# v1_1.net
KiCad netlist of a schematic drawn in EAGLE
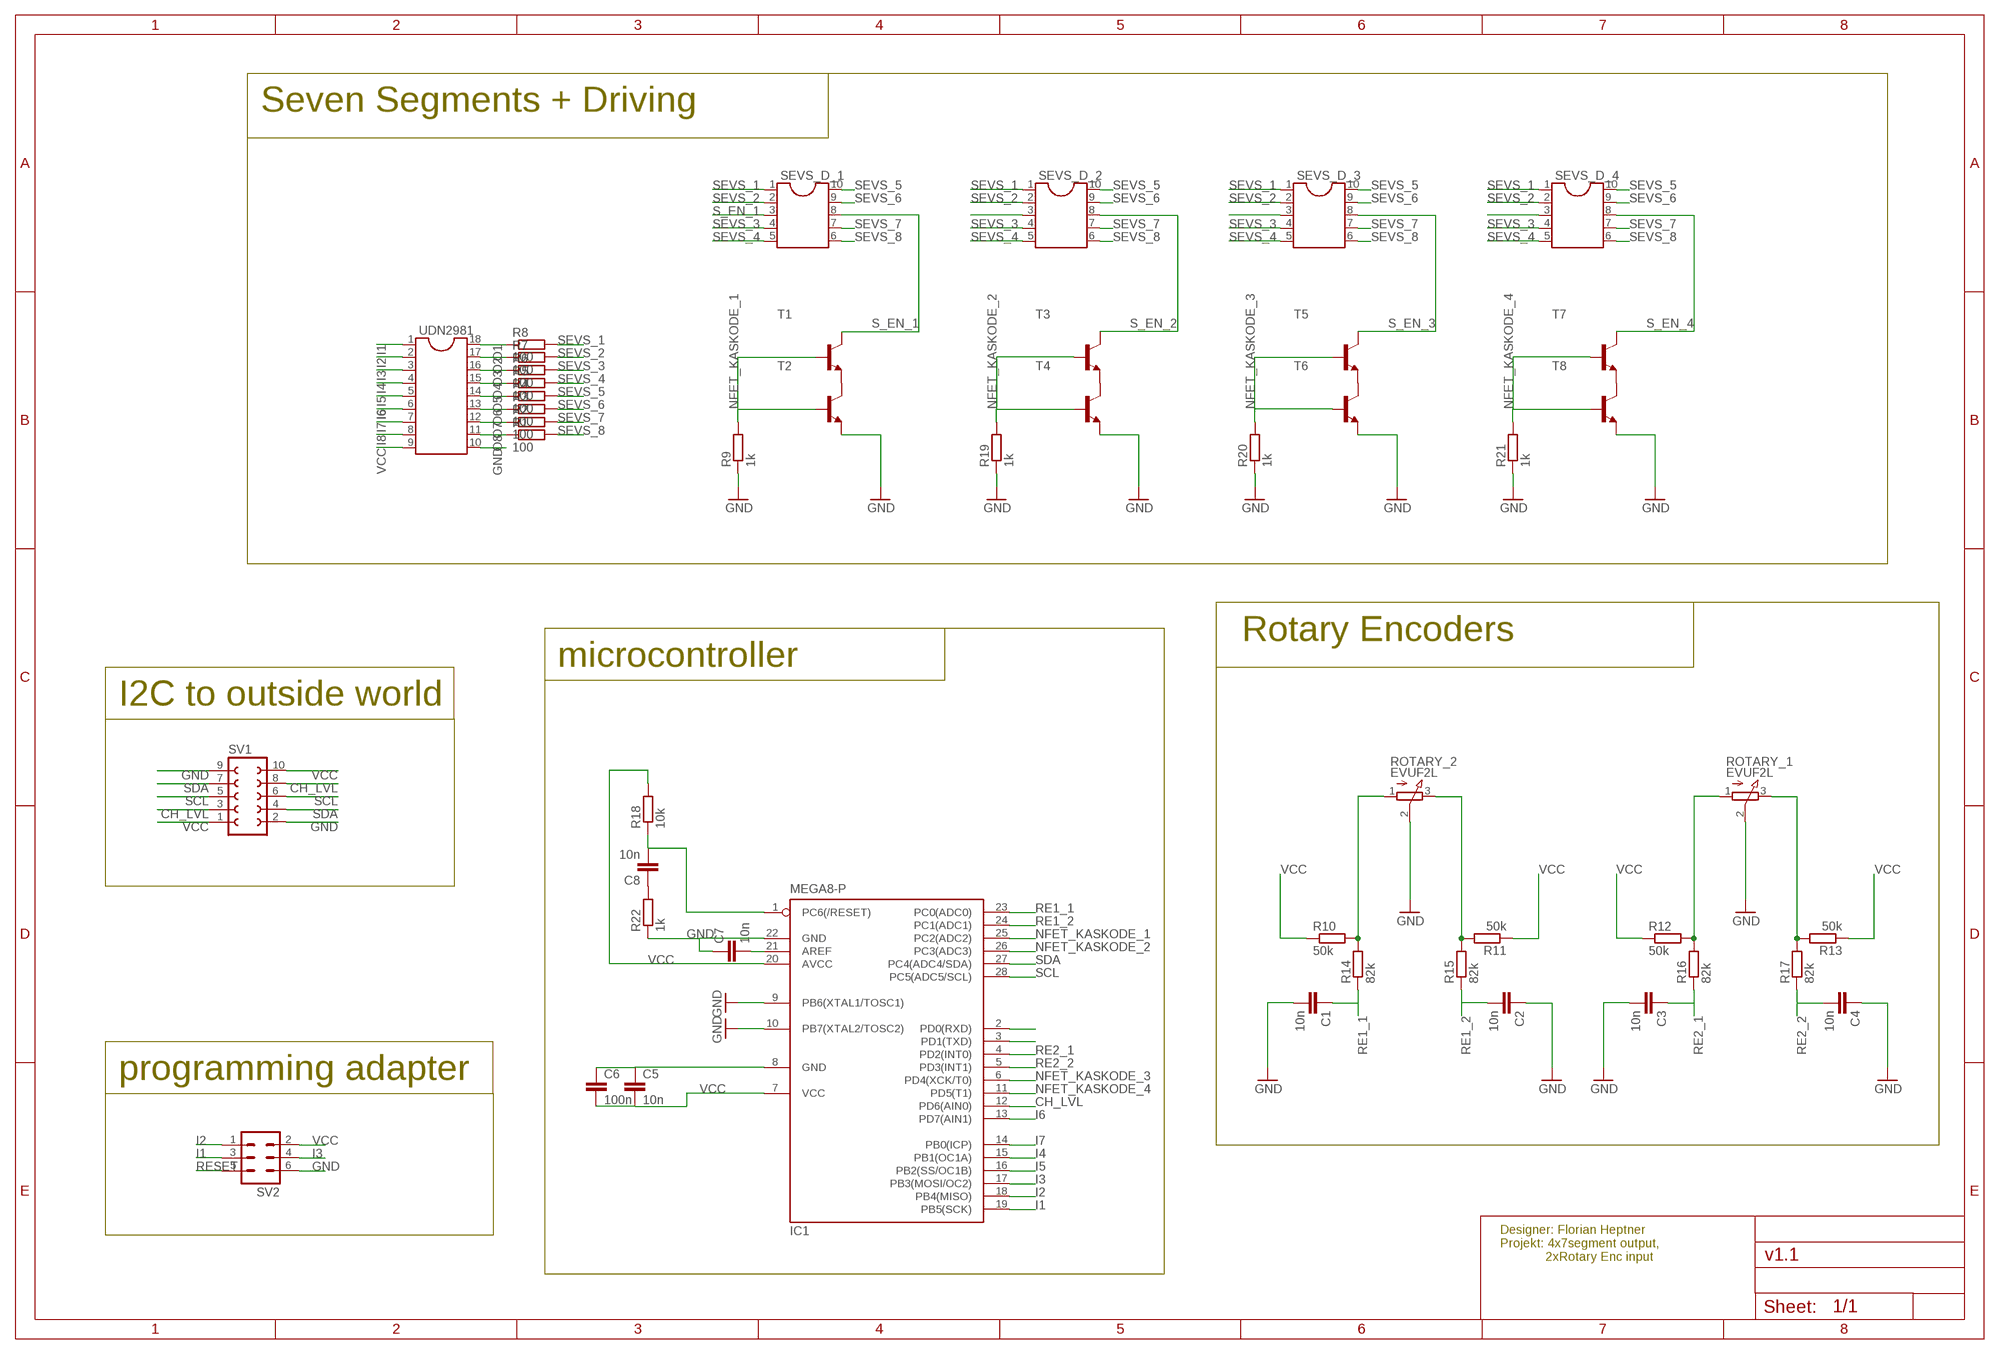
[diagram p0: schematic, sheet 1]

(export (version "E")
  (design (tool "Eeschema 10.0.6"))
  (components
    (comp (ref "C1")
      (value "10n")
      (footprint "eagle-import:C2.5-3")
      (libsource (lib "eagle-import") (part "C2,5-3"))
    )
    (comp (ref "C2")
      (value "10n")
      (footprint "eagle-import:C2.5-3")
      (libsource (lib "eagle-import") (part "C2,5-3"))
    )
    (comp (ref "C3")
      (value "10n")
      (footprint "eagle-import:C2.5-3")
      (libsource (lib "eagle-import") (part "C2,5-3"))
    )
    (comp (ref "C4")
      (value "10n")
      (footprint "eagle-import:C2.5-3")
      (libsource (lib "eagle-import") (part "C2,5-3"))
    )
    (comp (ref "C5")
      (value "10n")
      (footprint "eagle-import:C2.5-3")
      (libsource (lib "eagle-import") (part "C2,5-3"))
    )
    (comp (ref "C6")
      (value "100n")
      (footprint "eagle-import:C2.5-3")
      (libsource (lib "eagle-import") (part "C2,5-3"))
    )
    (comp (ref "C7")
      (value "10n")
      (footprint "eagle-import:C2.5-3")
      (libsource (lib "eagle-import") (part "C2,5-3"))
    )
    (comp (ref "C8")
      (value "10n")
      (footprint "eagle-import:C2.5-3")
      (libsource (lib "eagle-import") (part "C2,5-3"))
    )
    (comp (ref "IC1")
      (value "MEGA8-P")
      (footprint "eagle-import:DIL28-3")
      (libsource (lib "eagle-import") (part "MEGA8-P"))
    )
    (comp (ref "R1")
      (value "100")
      (footprint "eagle-import:0207_10")
      (libsource (lib "eagle-import") (part "R-EU_0207/10"))
    )
    (comp (ref "R2")
      (value "100")
      (footprint "eagle-import:0207_10")
      (libsource (lib "eagle-import") (part "R-EU_0207/10"))
    )
    (comp (ref "R3")
      (value "100")
      (footprint "eagle-import:0207_10")
      (libsource (lib "eagle-import") (part "R-EU_0207/10"))
    )
    (comp (ref "R4")
      (value "100")
      (footprint "eagle-import:0207_10")
      (libsource (lib "eagle-import") (part "R-EU_0207/10"))
    )
    (comp (ref "R5")
      (value "100")
      (footprint "eagle-import:0207_10")
      (libsource (lib "eagle-import") (part "R-EU_0207/10"))
    )
    (comp (ref "R6")
      (value "100")
      (footprint "eagle-import:0207_10")
      (libsource (lib "eagle-import") (part "R-EU_0207/10"))
    )
    (comp (ref "R7")
      (value "100")
      (footprint "eagle-import:0207_10")
      (libsource (lib "eagle-import") (part "R-EU_0207/10"))
    )
    (comp (ref "R8")
      (value "100")
      (footprint "eagle-import:0207_10")
      (libsource (lib "eagle-import") (part "R-EU_0207/10"))
    )
    (comp (ref "R9")
      (value "1k")
      (footprint "eagle-import:0207_10")
      (libsource (lib "eagle-import") (part "R-EU_0207/10"))
    )
    (comp (ref "R10")
      (value "50k")
      (footprint "eagle-import:0207_10")
      (libsource (lib "eagle-import") (part "R-EU_0207/10"))
    )
    (comp (ref "R11")
      (value "50k")
      (footprint "eagle-import:0207_10")
      (libsource (lib "eagle-import") (part "R-EU_0207/10"))
    )
    (comp (ref "R12")
      (value "50k")
      (footprint "eagle-import:0207_10")
      (libsource (lib "eagle-import") (part "R-EU_0207/10"))
    )
    (comp (ref "R13")
      (value "50k")
      (footprint "eagle-import:0207_10")
      (libsource (lib "eagle-import") (part "R-EU_0207/10"))
    )
    (comp (ref "R14")
      (value "82k")
      (footprint "eagle-import:0207_10")
      (libsource (lib "eagle-import") (part "R-EU_0207/10"))
    )
    (comp (ref "R15")
      (value "82k")
      (footprint "eagle-import:0207_10")
      (libsource (lib "eagle-import") (part "R-EU_0207/10"))
    )
    (comp (ref "R16")
      (value "82k")
      (footprint "eagle-import:0207_10")
      (libsource (lib "eagle-import") (part "R-EU_0207/10"))
    )
    (comp (ref "R17")
      (value "82k")
      (footprint "eagle-import:0207_10")
      (libsource (lib "eagle-import") (part "R-EU_0207/10"))
    )
    (comp (ref "R18")
      (value "10k")
      (footprint "eagle-import:0207_10")
      (libsource (lib "eagle-import") (part "R-EU_0207/10"))
    )
    (comp (ref "R19")
      (value "1k")
      (footprint "eagle-import:0207_10")
      (libsource (lib "eagle-import") (part "R-EU_0207/10"))
    )
    (comp (ref "R20")
      (value "1k")
      (footprint "eagle-import:0207_10")
      (libsource (lib "eagle-import") (part "R-EU_0207/10"))
    )
    (comp (ref "R21")
      (value "1k")
      (footprint "eagle-import:0207_10")
      (libsource (lib "eagle-import") (part "R-EU_0207/10"))
    )
    (comp (ref "R22")
      (value "1k")
      (footprint "eagle-import:0207_10")
      (libsource (lib "eagle-import") (part "R-EU_0207/10"))
    )
    (comp (ref "ROTARY_1")
      (value "EVUF2L")
      (footprint "eagle-import:EVUFXL")
      (libsource (lib "eagle-import") (part "EVULF2"))
    )
    (comp (ref "ROTARY_2")
      (value "EVUF2L")
      (footprint "eagle-import:EVUFXL")
      (libsource (lib "eagle-import") (part "EVULF2"))
    )
    (comp (ref "SEVS_D_1")
      (value "DIL10")
      (footprint "eagle-import:DIL10")
      (libsource (lib "eagle-import") (part "DIL10"))
    )
    (comp (ref "SEVS_D_2")
      (value "DIL10")
      (footprint "eagle-import:DIL10")
      (libsource (lib "eagle-import") (part "DIL10"))
    )
    (comp (ref "SEVS_D_3")
      (value "DIL10")
      (footprint "eagle-import:DIL10")
      (libsource (lib "eagle-import") (part "DIL10"))
    )
    (comp (ref "SEVS_D_4")
      (value "DIL10")
      (footprint "eagle-import:DIL10")
      (libsource (lib "eagle-import") (part "DIL10"))
    )
    (comp (ref "SV1")
      (value "FE05-2")
      (footprint "eagle-import:FE05-2")
      (libsource (lib "eagle-import") (part "FE05-2"))
    )
    (comp (ref "SV2")
      (value "ML6")
      (footprint "eagle-import:ML6")
      (libsource (lib "eagle-import") (part "ML6"))
    )
    (comp (ref "T1")
      (value "-NPN-TO92-CBE")
      (footprint "eagle-import:TO92-CBE")
      (libsource (lib "eagle-import") (part "-NPN-TO92-CBE"))
    )
    (comp (ref "T2")
      (value "-NPN-TO92-CBE")
      (footprint "eagle-import:TO92-CBE")
      (libsource (lib "eagle-import") (part "-NPN-TO92-CBE"))
    )
    (comp (ref "T3")
      (value "-NPN-TO92-CBE")
      (footprint "eagle-import:TO92-CBE")
      (libsource (lib "eagle-import") (part "-NPN-TO92-CBE"))
    )
    (comp (ref "T4")
      (value "-NPN-TO92-CBE")
      (footprint "eagle-import:TO92-CBE")
      (libsource (lib "eagle-import") (part "-NPN-TO92-CBE"))
    )
    (comp (ref "T5")
      (value "-NPN-TO92-CBE")
      (footprint "eagle-import:TO92-CBE")
      (libsource (lib "eagle-import") (part "-NPN-TO92-CBE"))
    )
    (comp (ref "T6")
      (value "-NPN-TO92-CBE")
      (footprint "eagle-import:TO92-CBE")
      (libsource (lib "eagle-import") (part "-NPN-TO92-CBE"))
    )
    (comp (ref "T7")
      (value "-NPN-TO92-CBE")
      (footprint "eagle-import:TO92-CBE")
      (libsource (lib "eagle-import") (part "-NPN-TO92-CBE"))
    )
    (comp (ref "T8")
      (value "-NPN-TO92-CBE")
      (footprint "eagle-import:TO92-CBE")
      (libsource (lib "eagle-import") (part "-NPN-TO92-CBE"))
    )
    (comp (ref "UDN2981")
      (value "DIL18")
      (footprint "eagle-import:DIL18")
      (libsource (lib "eagle-import") (part "DIL18"))
    )
  )
  (nets
    (net (code "1") (name "/CH_LVL") (class "Default")
      (node (ref "IC1") (pin "12") (pinfunction "PD6(AIN0)_12") (pintype "bidirectional"))
      (node (ref "SV1") (pin "3") (pinfunction "3_3") (pintype "passive"))
      (node (ref "SV1") (pin "8") (pinfunction "8_8") (pintype "passive"))
    )
    (net (code "2") (name "/I1") (class "Default")
      (node (ref "IC1") (pin "19") (pinfunction "PB5(SCK)_19") (pintype "bidirectional"))
      (node (ref "SV2") (pin "3") (pinfunction "3_3") (pintype "passive"))
      (node (ref "UDN2981") (pin "1") (pinfunction "1_1") (pintype "passive"))
    )
    (net (code "3") (name "/I2") (class "Default")
      (node (ref "IC1") (pin "18") (pinfunction "PB4(MISO)_18") (pintype "bidirectional"))
      (node (ref "SV2") (pin "1") (pinfunction "1_1") (pintype "passive"))
      (node (ref "UDN2981") (pin "2") (pinfunction "2_2") (pintype "passive"))
    )
    (net (code "4") (name "/I3") (class "Default")
      (node (ref "IC1") (pin "17") (pinfunction "PB3(MOSI/OC2)_17") (pintype "bidirectional"))
      (node (ref "SV2") (pin "4") (pinfunction "4_4") (pintype "passive"))
      (node (ref "UDN2981") (pin "3") (pinfunction "3_3") (pintype "passive"))
    )
    (net (code "5") (name "/I4") (class "Default")
      (node (ref "IC1") (pin "15") (pinfunction "PB1(OC1A)_15") (pintype "bidirectional"))
      (node (ref "UDN2981") (pin "4") (pinfunction "4_4") (pintype "passive"))
    )
    (net (code "6") (name "/I5") (class "Default")
      (node (ref "IC1") (pin "16") (pinfunction "PB2(SS/OC1B)_16") (pintype "bidirectional"))
      (node (ref "UDN2981") (pin "5") (pinfunction "5_5") (pintype "passive"))
    )
    (net (code "7") (name "/I6") (class "Default")
      (node (ref "IC1") (pin "13") (pinfunction "PD7(AIN1)_13") (pintype "bidirectional"))
      (node (ref "UDN2981") (pin "6") (pinfunction "6_6") (pintype "passive"))
    )
    (net (code "8") (name "/I7") (class "Default")
      (node (ref "IC1") (pin "14") (pinfunction "PB0(ICP)_14") (pintype "bidirectional"))
      (node (ref "UDN2981") (pin "7") (pinfunction "7_7") (pintype "passive"))
    )
    (net (code "9") (name "/I8") (class "Default")
      (node (ref "UDN2981") (pin "8") (pinfunction "8_8") (pintype "passive"))
    )
    (net (code "10") (name "/NFET_KASKODE_1") (class "Default")
      (node (ref "IC1") (pin "25") (pinfunction "PC2(ADC2)_25") (pintype "bidirectional"))
      (node (ref "R9") (pin "2") (pinfunction "2_2") (pintype "passive"))
      (node (ref "T1") (pin "B") (pinfunction "B_B") (pintype "passive"))
      (node (ref "T2") (pin "B") (pinfunction "B_B") (pintype "passive"))
    )
    (net (code "11") (name "/NFET_KASKODE_2") (class "Default")
      (node (ref "IC1") (pin "26") (pinfunction "PC3(ADC3)_26") (pintype "bidirectional"))
      (node (ref "R19") (pin "2") (pinfunction "2_2") (pintype "passive"))
      (node (ref "T3") (pin "B") (pinfunction "B_B") (pintype "passive"))
      (node (ref "T4") (pin "B") (pinfunction "B_B") (pintype "passive"))
    )
    (net (code "12") (name "/NFET_KASKODE_3") (class "Default")
      (node (ref "IC1") (pin "6") (pinfunction "PD4(XCK/T0)_6") (pintype "bidirectional"))
      (node (ref "R20") (pin "2") (pinfunction "2_2") (pintype "passive"))
      (node (ref "T5") (pin "B") (pinfunction "B_B") (pintype "passive"))
      (node (ref "T6") (pin "B") (pinfunction "B_B") (pintype "passive"))
    )
    (net (code "13") (name "/NFET_KASKODE_4") (class "Default")
      (node (ref "IC1") (pin "11") (pinfunction "PD5(T1)_11") (pintype "bidirectional"))
      (node (ref "R21") (pin "2") (pinfunction "2_2") (pintype "passive"))
      (node (ref "T7") (pin "B") (pinfunction "B_B") (pintype "passive"))
      (node (ref "T8") (pin "B") (pinfunction "B_B") (pintype "passive"))
    )
    (net (code "14") (name "/O1") (class "Default")
      (node (ref "R8") (pin "1") (pinfunction "1_1") (pintype "passive"))
      (node (ref "UDN2981") (pin "18") (pinfunction "18_18") (pintype "passive"))
    )
    (net (code "15") (name "/O2") (class "Default")
      (node (ref "R7") (pin "1") (pinfunction "1_1") (pintype "passive"))
      (node (ref "UDN2981") (pin "17") (pinfunction "17_17") (pintype "passive"))
    )
    (net (code "16") (name "/O3") (class "Default")
      (node (ref "R6") (pin "1") (pinfunction "1_1") (pintype "passive"))
      (node (ref "UDN2981") (pin "16") (pinfunction "16_16") (pintype "passive"))
    )
    (net (code "17") (name "/O4") (class "Default")
      (node (ref "R5") (pin "1") (pinfunction "1_1") (pintype "passive"))
      (node (ref "UDN2981") (pin "15") (pinfunction "15_15") (pintype "passive"))
    )
    (net (code "18") (name "/O5") (class "Default")
      (node (ref "R4") (pin "1") (pinfunction "1_1") (pintype "passive"))
      (node (ref "UDN2981") (pin "14") (pinfunction "14_14") (pintype "passive"))
    )
    (net (code "19") (name "/O6") (class "Default")
      (node (ref "R3") (pin "1") (pinfunction "1_1") (pintype "passive"))
      (node (ref "UDN2981") (pin "13") (pinfunction "13_13") (pintype "passive"))
    )
    (net (code "20") (name "/O7") (class "Default")
      (node (ref "R2") (pin "1") (pinfunction "1_1") (pintype "passive"))
      (node (ref "UDN2981") (pin "12") (pinfunction "12_12") (pintype "passive"))
    )
    (net (code "21") (name "/O8") (class "Default")
      (node (ref "R1") (pin "1") (pinfunction "1_1") (pintype "passive"))
      (node (ref "UDN2981") (pin "11") (pinfunction "11_11") (pintype "passive"))
    )
    (net (code "22") (name "/RE1_1") (class "Default")
      (node (ref "C1") (pin "1") (pinfunction "1_1") (pintype "passive"))
      (node (ref "IC1") (pin "23") (pinfunction "PC0(ADC0)_23") (pintype "bidirectional"))
      (node (ref "R14") (pin "1") (pinfunction "1_1") (pintype "passive"))
    )
    (net (code "23") (name "/RE1_2") (class "Default")
      (node (ref "C2") (pin "2") (pinfunction "2_2") (pintype "passive"))
      (node (ref "IC1") (pin "24") (pinfunction "PC1(ADC1)_24") (pintype "bidirectional"))
      (node (ref "R15") (pin "1") (pinfunction "1_1") (pintype "passive"))
    )
    (net (code "24") (name "/RE2_1") (class "Default")
      (node (ref "C3") (pin "1") (pinfunction "1_1") (pintype "passive"))
      (node (ref "IC1") (pin "4") (pinfunction "PD2(INT0)_4") (pintype "bidirectional"))
      (node (ref "R16") (pin "1") (pinfunction "1_1") (pintype "passive"))
    )
    (net (code "25") (name "/RE2_2") (class "Default")
      (node (ref "C4") (pin "2") (pinfunction "2_2") (pintype "passive"))
      (node (ref "IC1") (pin "5") (pinfunction "PD3(INT1)_5") (pintype "bidirectional"))
      (node (ref "R17") (pin "1") (pinfunction "1_1") (pintype "passive"))
    )
    (net (code "26") (name "/RESET") (class "Default")
      (node (ref "C8") (pin "2") (pinfunction "2_2") (pintype "passive"))
      (node (ref "IC1") (pin "1") (pinfunction "PC6(/RESET)_1") (pintype "bidirectional"))
      (node (ref "R18") (pin "1") (pinfunction "1_1") (pintype "passive"))
      (node (ref "SV2") (pin "5") (pinfunction "5_5") (pintype "passive"))
    )
    (net (code "27") (name "/SCL") (class "Default")
      (node (ref "IC1") (pin "28") (pinfunction "PC5(ADC5/SCL)_28") (pintype "bidirectional"))
      (node (ref "SV1") (pin "5") (pinfunction "5_5") (pintype "passive"))
      (node (ref "SV1") (pin "6") (pinfunction "6_6") (pintype "passive"))
    )
    (net (code "28") (name "/SDA") (class "Default")
      (node (ref "IC1") (pin "27") (pinfunction "PC4(ADC4/SDA)_27") (pintype "bidirectional"))
      (node (ref "SV1") (pin "4") (pinfunction "4_4") (pintype "passive"))
      (node (ref "SV1") (pin "7") (pinfunction "7_7") (pintype "passive"))
    )
    (net (code "29") (name "/SEVS_1") (class "Default")
      (node (ref "R8") (pin "2") (pinfunction "2_2") (pintype "passive"))
      (node (ref "SEVS_D_1") (pin "1") (pinfunction "1_1") (pintype "passive"))
      (node (ref "SEVS_D_2") (pin "1") (pinfunction "1_1") (pintype "passive"))
      (node (ref "SEVS_D_3") (pin "1") (pinfunction "1_1") (pintype "passive"))
      (node (ref "SEVS_D_4") (pin "1") (pinfunction "1_1") (pintype "passive"))
    )
    (net (code "30") (name "/SEVS_2") (class "Default")
      (node (ref "R7") (pin "2") (pinfunction "2_2") (pintype "passive"))
      (node (ref "SEVS_D_1") (pin "2") (pinfunction "2_2") (pintype "passive"))
      (node (ref "SEVS_D_2") (pin "2") (pinfunction "2_2") (pintype "passive"))
      (node (ref "SEVS_D_3") (pin "2") (pinfunction "2_2") (pintype "passive"))
      (node (ref "SEVS_D_4") (pin "2") (pinfunction "2_2") (pintype "passive"))
    )
    (net (code "31") (name "/SEVS_3") (class "Default")
      (node (ref "R6") (pin "2") (pinfunction "2_2") (pintype "passive"))
      (node (ref "SEVS_D_1") (pin "4") (pinfunction "4_4") (pintype "passive"))
      (node (ref "SEVS_D_2") (pin "4") (pinfunction "4_4") (pintype "passive"))
      (node (ref "SEVS_D_3") (pin "4") (pinfunction "4_4") (pintype "passive"))
      (node (ref "SEVS_D_4") (pin "4") (pinfunction "4_4") (pintype "passive"))
    )
    (net (code "32") (name "/SEVS_4") (class "Default")
      (node (ref "R5") (pin "2") (pinfunction "2_2") (pintype "passive"))
      (node (ref "SEVS_D_1") (pin "5") (pinfunction "5_5") (pintype "passive"))
      (node (ref "SEVS_D_2") (pin "5") (pinfunction "5_5") (pintype "passive"))
      (node (ref "SEVS_D_3") (pin "5") (pinfunction "5_5") (pintype "passive"))
      (node (ref "SEVS_D_4") (pin "5") (pinfunction "5_5") (pintype "passive"))
    )
    (net (code "33") (name "/SEVS_5") (class "Default")
      (node (ref "R4") (pin "2") (pinfunction "2_2") (pintype "passive"))
      (node (ref "SEVS_D_1") (pin "10") (pinfunction "10_10") (pintype "passive"))
      (node (ref "SEVS_D_2") (pin "10") (pinfunction "10_10") (pintype "passive"))
      (node (ref "SEVS_D_3") (pin "10") (pinfunction "10_10") (pintype "passive"))
      (node (ref "SEVS_D_4") (pin "10") (pinfunction "10_10") (pintype "passive"))
    )
    (net (code "34") (name "/SEVS_6") (class "Default")
      (node (ref "R3") (pin "2") (pinfunction "2_2") (pintype "passive"))
      (node (ref "SEVS_D_1") (pin "9") (pinfunction "9_9") (pintype "passive"))
      (node (ref "SEVS_D_2") (pin "9") (pinfunction "9_9") (pintype "passive"))
      (node (ref "SEVS_D_3") (pin "9") (pinfunction "9_9") (pintype "passive"))
      (node (ref "SEVS_D_4") (pin "9") (pinfunction "9_9") (pintype "passive"))
    )
    (net (code "35") (name "/SEVS_7") (class "Default")
      (node (ref "R2") (pin "2") (pinfunction "2_2") (pintype "passive"))
      (node (ref "SEVS_D_1") (pin "7") (pinfunction "7_7") (pintype "passive"))
      (node (ref "SEVS_D_2") (pin "7") (pinfunction "7_7") (pintype "passive"))
      (node (ref "SEVS_D_3") (pin "7") (pinfunction "7_7") (pintype "passive"))
      (node (ref "SEVS_D_4") (pin "7") (pinfunction "7_7") (pintype "passive"))
    )
    (net (code "36") (name "/SEVS_8") (class "Default")
      (node (ref "R1") (pin "2") (pinfunction "2_2") (pintype "passive"))
      (node (ref "SEVS_D_1") (pin "6") (pinfunction "6_6") (pintype "passive"))
      (node (ref "SEVS_D_2") (pin "6") (pinfunction "6_6") (pintype "passive"))
      (node (ref "SEVS_D_3") (pin "6") (pinfunction "6_6") (pintype "passive"))
      (node (ref "SEVS_D_4") (pin "6") (pinfunction "6_6") (pintype "passive"))
    )
    (net (code "37") (name "/S_EN_1") (class "Default")
      (node (ref "SEVS_D_1") (pin "3") (pinfunction "3_3") (pintype "passive"))
      (node (ref "SEVS_D_1") (pin "8") (pinfunction "8_8") (pintype "passive"))
      (node (ref "T1") (pin "C") (pinfunction "C_C") (pintype "passive"))
    )
    (net (code "38") (name "/S_EN_2") (class "Default")
      (node (ref "SEVS_D_2") (pin "3") (pinfunction "3_3") (pintype "passive"))
      (node (ref "SEVS_D_2") (pin "8") (pinfunction "8_8") (pintype "passive"))
      (node (ref "T3") (pin "C") (pinfunction "C_C") (pintype "passive"))
    )
    (net (code "39") (name "/S_EN_3") (class "Default")
      (node (ref "SEVS_D_3") (pin "3") (pinfunction "3_3") (pintype "passive"))
      (node (ref "SEVS_D_3") (pin "8") (pinfunction "8_8") (pintype "passive"))
      (node (ref "T5") (pin "C") (pinfunction "C_C") (pintype "passive"))
    )
    (net (code "40") (name "/S_EN_4") (class "Default")
      (node (ref "SEVS_D_4") (pin "3") (pinfunction "3_3") (pintype "passive"))
      (node (ref "SEVS_D_4") (pin "8") (pinfunction "8_8") (pintype "passive"))
      (node (ref "T7") (pin "C") (pinfunction "C_C") (pintype "passive"))
    )
    (net (code "41") (name "/VCC") (class "Default")
      (node (ref "C5") (pin "2") (pinfunction "2_2") (pintype "passive"))
      (node (ref "C6") (pin "2") (pinfunction "2_2") (pintype "passive"))
      (node (ref "IC1") (pin "20") (pinfunction "AVCC_20") (pintype "power_in"))
      (node (ref "IC1") (pin "7") (pinfunction "VCC_7") (pintype "power_in"))
      (node (ref "R10") (pin "1") (pinfunction "1_1") (pintype "passive"))
      (node (ref "R11") (pin "1") (pinfunction "1_1") (pintype "passive"))
      (node (ref "R12") (pin "1") (pinfunction "1_1") (pintype "passive"))
      (node (ref "R13") (pin "1") (pinfunction "1_1") (pintype "passive"))
      (node (ref "R18") (pin "2") (pinfunction "2_2") (pintype "passive"))
      (node (ref "SV1") (pin "1") (pinfunction "1_1") (pintype "passive"))
      (node (ref "SV1") (pin "10") (pinfunction "10_10") (pintype "passive"))
      (node (ref "SV2") (pin "2") (pinfunction "2_2") (pintype "passive"))
      (node (ref "UDN2981") (pin "9") (pinfunction "9_9") (pintype "passive"))
    )
    (net (code "42") (name "GND") (class "Default")
      (node (ref "C1") (pin "2") (pinfunction "2_2") (pintype "passive"))
      (node (ref "C2") (pin "1") (pinfunction "1_1") (pintype "passive"))
      (node (ref "C3") (pin "2") (pinfunction "2_2") (pintype "passive"))
      (node (ref "C4") (pin "1") (pinfunction "1_1") (pintype "passive"))
      (node (ref "C7") (pin "1") (pinfunction "1_1") (pintype "passive"))
      (node (ref "IC1") (pin "10") (pinfunction "PB7(XTAL2/TOSC2)_10") (pintype "bidirectional"))
      (node (ref "IC1") (pin "22") (pinfunction "GND_22") (pintype "power_in"))
      (node (ref "IC1") (pin "9") (pinfunction "PB6(XTAL1/TOSC1)_9") (pintype "bidirectional"))
      (node (ref "R19") (pin "1") (pinfunction "1_1") (pintype "passive"))
      (node (ref "R20") (pin "1") (pinfunction "1_1") (pintype "passive"))
      (node (ref "R21") (pin "1") (pinfunction "1_1") (pintype "passive"))
      (node (ref "R22") (pin "1") (pinfunction "1_1") (pintype "passive"))
      (node (ref "R9") (pin "1") (pinfunction "1_1") (pintype "passive"))
      (node (ref "ROTARY_1") (pin "2") (pinfunction "S_2") (pintype "passive"))
      (node (ref "ROTARY_2") (pin "2") (pinfunction "S_2") (pintype "passive"))
      (node (ref "SV1") (pin "2") (pinfunction "2_2") (pintype "passive"))
      (node (ref "SV1") (pin "9") (pinfunction "9_9") (pintype "passive"))
      (node (ref "SV2") (pin "6") (pinfunction "6_6") (pintype "passive"))
      (node (ref "T2") (pin "E") (pinfunction "E_E") (pintype "passive"))
      (node (ref "T4") (pin "E") (pinfunction "E_E") (pintype "passive"))
      (node (ref "T6") (pin "E") (pinfunction "E_E") (pintype "passive"))
      (node (ref "T8") (pin "E") (pinfunction "E_E") (pintype "passive"))
      (node (ref "UDN2981") (pin "10") (pinfunction "10_10") (pintype "passive"))
    )
    (net (code "43") (name "Net-(C5-Pad1)") (class "Default")
      (node (ref "C5") (pin "1") (pinfunction "1_1") (pintype "passive"))
      (node (ref "C6") (pin "1") (pinfunction "1_1") (pintype "passive"))
      (node (ref "IC1") (pin "8") (pinfunction "GND_8") (pintype "power_in"))
    )
    (net (code "44") (name "Net-(C8-Pad1)") (class "Default")
      (node (ref "C8") (pin "1") (pinfunction "1_1") (pintype "passive"))
      (node (ref "R22") (pin "2") (pinfunction "2_2") (pintype "passive"))
    )
    (net (code "45") (name "Net-(IC1-AREF)") (class "Default")
      (node (ref "C7") (pin "2") (pinfunction "2_2") (pintype "passive"))
      (node (ref "IC1") (pin "21") (pinfunction "AREF_21") (pintype "passive"))
    )
    (net (code "46") (name "Net-(ROTARY_1-A)") (class "Default")
      (node (ref "R12") (pin "2") (pinfunction "2_2") (pintype "passive"))
      (node (ref "R16") (pin "2") (pinfunction "2_2") (pintype "passive"))
      (node (ref "ROTARY_1") (pin "1") (pinfunction "A_1") (pintype "passive"))
    )
    (net (code "47") (name "Net-(ROTARY_1-E)") (class "Default")
      (node (ref "R13") (pin "2") (pinfunction "2_2") (pintype "passive"))
      (node (ref "R17") (pin "2") (pinfunction "2_2") (pintype "passive"))
      (node (ref "ROTARY_1") (pin "3") (pinfunction "E_3") (pintype "passive"))
    )
    (net (code "48") (name "Net-(ROTARY_2-A)") (class "Default")
      (node (ref "R10") (pin "2") (pinfunction "2_2") (pintype "passive"))
      (node (ref "R14") (pin "2") (pinfunction "2_2") (pintype "passive"))
      (node (ref "ROTARY_2") (pin "1") (pinfunction "A_1") (pintype "passive"))
    )
    (net (code "49") (name "Net-(ROTARY_2-E)") (class "Default")
      (node (ref "R11") (pin "2") (pinfunction "2_2") (pintype "passive"))
      (node (ref "R15") (pin "2") (pinfunction "2_2") (pintype "passive"))
      (node (ref "ROTARY_2") (pin "3") (pinfunction "E_3") (pintype "passive"))
    )
    (net (code "50") (name "Net-(T1-PadE)") (class "Default")
      (node (ref "T1") (pin "E") (pinfunction "E_E") (pintype "passive"))
      (node (ref "T2") (pin "C") (pinfunction "C_C") (pintype "passive"))
    )
    (net (code "51") (name "Net-(T3-PadE)") (class "Default")
      (node (ref "T3") (pin "E") (pinfunction "E_E") (pintype "passive"))
      (node (ref "T4") (pin "C") (pinfunction "C_C") (pintype "passive"))
    )
    (net (code "52") (name "Net-(T5-PadE)") (class "Default")
      (node (ref "T5") (pin "E") (pinfunction "E_E") (pintype "passive"))
      (node (ref "T6") (pin "C") (pinfunction "C_C") (pintype "passive"))
    )
    (net (code "53") (name "Net-(T7-PadE)") (class "Default")
      (node (ref "T7") (pin "E") (pinfunction "E_E") (pintype "passive"))
      (node (ref "T8") (pin "C") (pinfunction "C_C") (pintype "passive"))
    )
    (net (code "54") (name "unconnected-(IC1-PD0(RXD)-Pad2)") (class "Default")
      (node (ref "IC1") (pin "2") (pinfunction "PD0(RXD)_2") (pintype "bidirectional"))
    )
    (net (code "55") (name "unconnected-(IC1-PD1(TXD)-Pad3)") (class "Default")
      (node (ref "IC1") (pin "3") (pinfunction "PD1(TXD)_3") (pintype "bidirectional"))
    )
  )
)
